# esp-12-f-breakout-ch340t.net
KiCad netlist of a schematic drawn in EAGLE
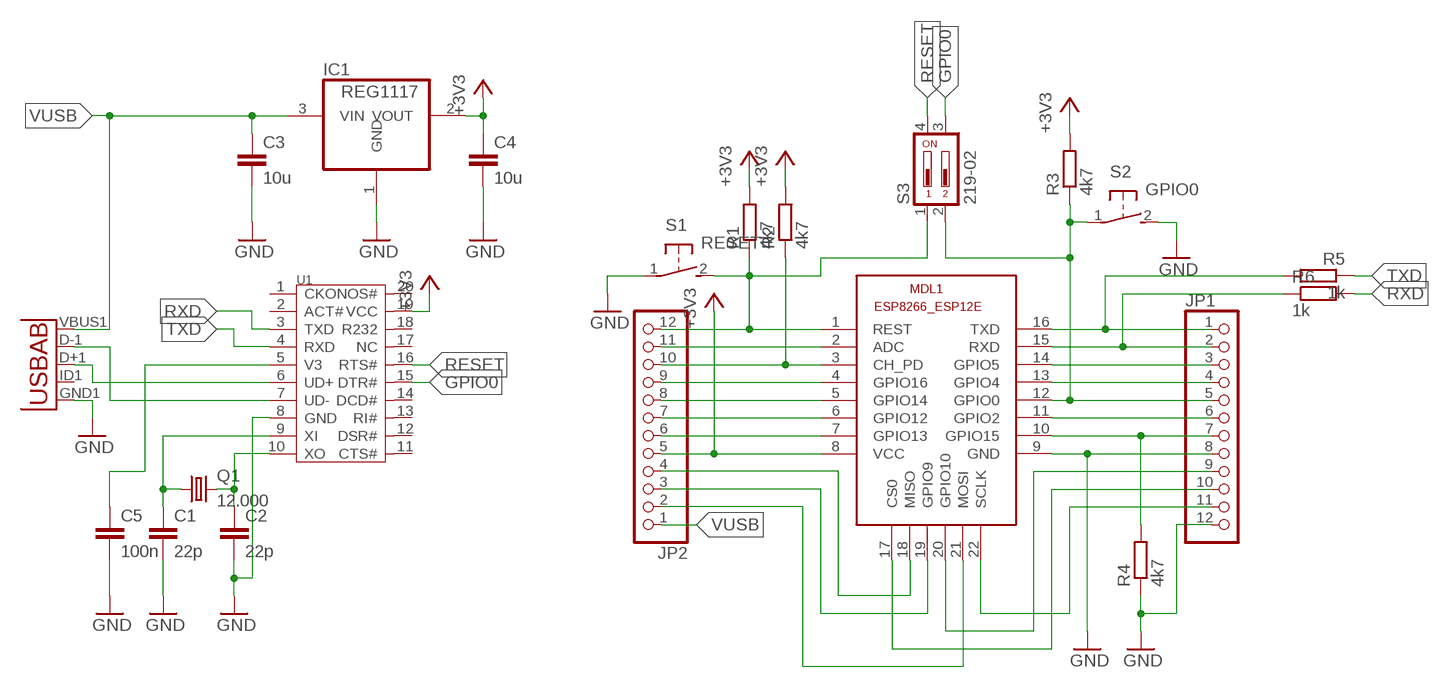
[diagram p0: schematic, sheet 1]

(export (version "E")
  (design (tool "Eeschema 10.0.6"))
  (components
    (comp (ref "C1")
      (value "22p")
      (footprint "eagle-import:C0805")
      (libsource (lib "eagle-import") (part "C-EUC0805"))
    )
    (comp (ref "C2")
      (value "22p")
      (footprint "eagle-import:C0805")
      (libsource (lib "eagle-import") (part "C-EUC0805"))
    )
    (comp (ref "C3")
      (value "10u")
      (footprint "eagle-import:C0805")
      (libsource (lib "eagle-import") (part "C-EUC0805"))
    )
    (comp (ref "C4")
      (value "10u")
      (footprint "eagle-import:C0805")
      (libsource (lib "eagle-import") (part "C-EUC0805"))
    )
    (comp (ref "C5")
      (value "100n")
      (footprint "eagle-import:C0805")
      (libsource (lib "eagle-import") (part "C-EUC0805"))
    )
    (comp (ref "IC1")
      (value "REG1117")
      (footprint "eagle-import:SOT223")
      (libsource (lib "eagle-import") (part "REG1117"))
    )
    (comp (ref "JP1")
      (value "PINHD-1X12")
      (footprint "eagle-import:1X12")
      (libsource (lib "eagle-import") (part "PINHD-1X12"))
    )
    (comp (ref "JP2")
      (value "PINHD-1X12")
      (footprint "eagle-import:1X12")
      (libsource (lib "eagle-import") (part "PINHD-1X12"))
    )
    (comp (ref "MDL1")
      (value "ESP8266-12EESP8266-ESP12E")
      (footprint "eagle-import:ESP8266-ESP12E")
      (libsource (lib "eagle-import") (part "ESP8266-12EESP8266-ESP12E"))
    )
    (comp (ref "Q1")
      (value "12.000")
      (footprint "eagle-import:HC49UP")
      (libsource (lib "eagle-import") (part "CRYSTALHC49UP"))
    )
    (comp (ref "R1")
      (value "4k7")
      (footprint "eagle-import:M0805")
      (libsource (lib "eagle-import") (part "R-EU_M0805"))
    )
    (comp (ref "R2")
      (value "4k7")
      (footprint "eagle-import:M0805")
      (libsource (lib "eagle-import") (part "R-EU_M0805"))
    )
    (comp (ref "R3")
      (value "4k7")
      (footprint "eagle-import:M0805")
      (libsource (lib "eagle-import") (part "R-EU_M0805"))
    )
    (comp (ref "R4")
      (value "4k7")
      (footprint "eagle-import:M0805")
      (libsource (lib "eagle-import") (part "R-EU_M0805"))
    )
    (comp (ref "R5")
      (value "1k")
      (footprint "eagle-import:M0805")
      (libsource (lib "eagle-import") (part "R-EU_M0805"))
    )
    (comp (ref "R6")
      (value "1k")
      (footprint "eagle-import:M0805")
      (libsource (lib "eagle-import") (part "R-EU_M0805"))
    )
    (comp (ref "S1")
      (value "RESET")
      (footprint "eagle-import:DTSM-3")
      (libsource (lib "eagle-import") (part "DTSM-3"))
    )
    (comp (ref "S2")
      (value "GPIO0")
      (footprint "eagle-import:DTSM-3")
      (libsource (lib "eagle-import") (part "DTSM-3"))
    )
    (comp (ref "S3")
      (value "219-02")
      (footprint "eagle-import:CTS-219-02")
      (libsource (lib "eagle-import") (part "219-02"))
    )
    (comp (ref "U1")
      (value "CH340T")
      (footprint "eagle-import:SSOP20")
      (libsource (lib "eagle-import") (part "CH340T"))
    )
    (comp (ref "U2")
      (value "USB\"\"")
      (footprint "eagle-import:USB-MICRO-SMD")
      (libsource (lib "eagle-import") (part "USB{dblquote}{dblquote}"))
    )
  )
  (nets
    (net (code "1") (name "+3V3") (class "Default")
      (node (ref "C4") (pin "1") (pinfunction "1_1") (pintype "passive"))
      (node (ref "IC1") (pin "2") (pinfunction "VOUT_2") (pintype "output"))
      (node (ref "JP2") (pin "5") (pinfunction "5_5") (pintype "passive"))
      (node (ref "MDL1") (pin "8") (pinfunction "VCC_8") (pintype "bidirectional"))
      (node (ref "R1") (pin "2") (pinfunction "2_2") (pintype "passive"))
      (node (ref "R2") (pin "2") (pinfunction "2_2") (pintype "passive"))
      (node (ref "R3") (pin "2") (pinfunction "2_2") (pintype "passive"))
      (node (ref "U1") (pin "19") (pinfunction "VCC_19") (pintype "power_in"))
    )
    (net (code "2") (name "/NOS#") (class "Default")
      (node (ref "U1") (pin "20") (pinfunction "NOS#_20") (pintype "power_in"))
    )
    (net (code "3") (name "GND") (class "Default")
      (node (ref "C1") (pin "2") (pinfunction "2_2") (pintype "passive"))
      (node (ref "C2") (pin "2") (pinfunction "2_2") (pintype "passive"))
      (node (ref "C3") (pin "2") (pinfunction "2_2") (pintype "passive"))
      (node (ref "C4") (pin "2") (pinfunction "2_2") (pintype "passive"))
      (node (ref "C5") (pin "2") (pinfunction "2_2") (pintype "passive"))
      (node (ref "IC1") (pin "1") (pinfunction "GND_1") (pintype "power_in"))
      (node (ref "JP1") (pin "12") (pinfunction "12_12") (pintype "passive"))
      (node (ref "JP1") (pin "8") (pinfunction "8_8") (pintype "passive"))
      (node (ref "MDL1") (pin "9") (pinfunction "GND_9") (pintype "bidirectional"))
      (node (ref "R4") (pin "1") (pinfunction "1_1") (pintype "passive"))
      (node (ref "S1") (pin "1") (pinfunction "1_1") (pintype "passive"))
      (node (ref "S2") (pin "2") (pinfunction "2_2") (pintype "passive"))
      (node (ref "U1") (pin "8") (pinfunction "GND_8") (pintype "power_in"))
      (node (ref "U2") (pin "GND1") (pinfunction "GND_GND1") (pintype "bidirectional"))
    )
    (net (code "4") (name "GPIO0") (class "Default")
      (node (ref "S3") (pin "3") (pinfunction "3_3") (pintype "passive"))
      (node (ref "U1") (pin "15") (pinfunction "DTR#_15") (pintype "output"))
    )
    (net (code "5") (name "Net-(MDL1-ADC)") (class "Default")
      (node (ref "JP2") (pin "11") (pinfunction "11_11") (pintype "passive"))
      (node (ref "MDL1") (pin "2") (pinfunction "ADC_2") (pintype "bidirectional"))
    )
    (net (code "6") (name "Net-(MDL1-CH_PD)") (class "Default")
      (node (ref "JP2") (pin "10") (pinfunction "10_10") (pintype "passive"))
      (node (ref "MDL1") (pin "3") (pinfunction "CH_PD_3") (pintype "bidirectional"))
      (node (ref "R2") (pin "1") (pinfunction "1_1") (pintype "passive"))
    )
    (net (code "7") (name "Net-(MDL1-CS0)") (class "Default")
      (node (ref "JP1") (pin "10") (pinfunction "10_10") (pintype "passive"))
      (node (ref "MDL1") (pin "17") (pinfunction "CS0_17") (pintype "bidirectional"))
    )
    (net (code "8") (name "Net-(MDL1-GPIO0)") (class "Default")
      (node (ref "JP1") (pin "5") (pinfunction "5_5") (pintype "passive"))
      (node (ref "MDL1") (pin "12") (pinfunction "GPIO0_12") (pintype "bidirectional"))
      (node (ref "R3") (pin "1") (pinfunction "1_1") (pintype "passive"))
      (node (ref "S2") (pin "1") (pinfunction "1_1") (pintype "passive"))
      (node (ref "S3") (pin "2") (pinfunction "2_2") (pintype "passive"))
    )
    (net (code "9") (name "Net-(MDL1-GPIO2)") (class "Default")
      (node (ref "JP1") (pin "6") (pinfunction "6_6") (pintype "passive"))
      (node (ref "MDL1") (pin "11") (pinfunction "GPIO2_11") (pintype "bidirectional"))
    )
    (net (code "10") (name "Net-(MDL1-GPIO4)") (class "Default")
      (node (ref "JP1") (pin "4") (pinfunction "4_4") (pintype "passive"))
      (node (ref "MDL1") (pin "13") (pinfunction "GPIO4_13") (pintype "bidirectional"))
    )
    (net (code "11") (name "Net-(MDL1-GPIO5)") (class "Default")
      (node (ref "JP1") (pin "3") (pinfunction "3_3") (pintype "passive"))
      (node (ref "MDL1") (pin "14") (pinfunction "GPIO5_14") (pintype "bidirectional"))
    )
    (net (code "12") (name "Net-(MDL1-GPIO9)") (class "Default")
      (node (ref "JP2") (pin "3") (pinfunction "3_3") (pintype "passive"))
      (node (ref "MDL1") (pin "19") (pinfunction "GPIO9_19") (pintype "bidirectional"))
    )
    (net (code "13") (name "Net-(MDL1-GPIO10)") (class "Default")
      (node (ref "JP1") (pin "9") (pinfunction "9_9") (pintype "passive"))
      (node (ref "MDL1") (pin "20") (pinfunction "GPIO10_20") (pintype "bidirectional"))
    )
    (net (code "14") (name "Net-(MDL1-GPIO12)") (class "Default")
      (node (ref "JP2") (pin "7") (pinfunction "7_7") (pintype "passive"))
      (node (ref "MDL1") (pin "6") (pinfunction "GPIO12_6") (pintype "bidirectional"))
    )
    (net (code "15") (name "Net-(MDL1-GPIO13)") (class "Default")
      (node (ref "JP2") (pin "6") (pinfunction "6_6") (pintype "passive"))
      (node (ref "MDL1") (pin "7") (pinfunction "GPIO13_7") (pintype "bidirectional"))
    )
    (net (code "16") (name "Net-(MDL1-GPIO14)") (class "Default")
      (node (ref "JP2") (pin "8") (pinfunction "8_8") (pintype "passive"))
      (node (ref "MDL1") (pin "5") (pinfunction "GPIO14_5") (pintype "bidirectional"))
    )
    (net (code "17") (name "Net-(MDL1-GPIO15)") (class "Default")
      (node (ref "JP1") (pin "7") (pinfunction "7_7") (pintype "passive"))
      (node (ref "MDL1") (pin "10") (pinfunction "GPIO15_10") (pintype "bidirectional"))
      (node (ref "R4") (pin "2") (pinfunction "2_2") (pintype "passive"))
    )
    (net (code "18") (name "Net-(MDL1-GPIO16)") (class "Default")
      (node (ref "JP2") (pin "9") (pinfunction "9_9") (pintype "passive"))
      (node (ref "MDL1") (pin "4") (pinfunction "GPIO16_4") (pintype "bidirectional"))
    )
    (net (code "19") (name "Net-(MDL1-MISO)") (class "Default")
      (node (ref "JP2") (pin "4") (pinfunction "4_4") (pintype "passive"))
      (node (ref "MDL1") (pin "18") (pinfunction "MISO_18") (pintype "bidirectional"))
    )
    (net (code "20") (name "Net-(MDL1-MOSI)") (class "Default")
      (node (ref "JP2") (pin "2") (pinfunction "2_2") (pintype "passive"))
      (node (ref "MDL1") (pin "21") (pinfunction "MOSI_21") (pintype "bidirectional"))
    )
    (net (code "21") (name "Net-(MDL1-REST)") (class "Default")
      (node (ref "JP2") (pin "12") (pinfunction "12_12") (pintype "passive"))
      (node (ref "MDL1") (pin "1") (pinfunction "REST_1") (pintype "bidirectional"))
      (node (ref "R1") (pin "1") (pinfunction "1_1") (pintype "passive"))
      (node (ref "S1") (pin "2") (pinfunction "2_2") (pintype "passive"))
      (node (ref "S3") (pin "1") (pinfunction "1_1") (pintype "passive"))
    )
    (net (code "22") (name "Net-(MDL1-RXD)") (class "Default")
      (node (ref "JP1") (pin "2") (pinfunction "2_2") (pintype "passive"))
      (node (ref "MDL1") (pin "15") (pinfunction "RXD_15") (pintype "bidirectional"))
      (node (ref "R6") (pin "1") (pinfunction "1_1") (pintype "passive"))
    )
    (net (code "23") (name "Net-(MDL1-SCLK)") (class "Default")
      (node (ref "JP1") (pin "11") (pinfunction "11_11") (pintype "passive"))
      (node (ref "MDL1") (pin "22") (pinfunction "SCLK_22") (pintype "bidirectional"))
    )
    (net (code "24") (name "Net-(MDL1-TXD)") (class "Default")
      (node (ref "JP1") (pin "1") (pinfunction "1_1") (pintype "passive"))
      (node (ref "MDL1") (pin "16") (pinfunction "TXD_16") (pintype "bidirectional"))
      (node (ref "R5") (pin "2") (pinfunction "2_2") (pintype "passive"))
    )
    (net (code "25") (name "Net-(U1-UD+)") (class "Default")
      (node (ref "U1") (pin "6") (pinfunction "UD+_6") (pintype "bidirectional"))
      (node (ref "U2") (pin "D+1") (pinfunction "D+_D+1") (pintype "bidirectional"))
    )
    (net (code "26") (name "Net-(U1-UD-)") (class "Default")
      (node (ref "U1") (pin "7") (pinfunction "UD-_7") (pintype "bidirectional"))
      (node (ref "U2") (pin "D-1") (pinfunction "D-_D-1") (pintype "bidirectional"))
    )
    (net (code "27") (name "Net-(U1-V3)") (class "Default")
      (node (ref "C5") (pin "1") (pinfunction "1_1") (pintype "passive"))
      (node (ref "U1") (pin "5") (pinfunction "V3_5") (pintype "power_in"))
    )
    (net (code "28") (name "Net-(U1-XI)") (class "Default")
      (node (ref "C1") (pin "1") (pinfunction "1_1") (pintype "passive"))
      (node (ref "Q1") (pin "1") (pinfunction "1_1") (pintype "passive"))
      (node (ref "U1") (pin "9") (pinfunction "XI_9") (pintype "input"))
    )
    (net (code "29") (name "Net-(U1-XO)") (class "Default")
      (node (ref "C2") (pin "1") (pinfunction "1_1") (pintype "passive"))
      (node (ref "Q1") (pin "2") (pinfunction "2_2") (pintype "passive"))
      (node (ref "U1") (pin "10") (pinfunction "XO_10") (pintype "output"))
    )
    (net (code "30") (name "RESET") (class "Default")
      (node (ref "S3") (pin "4") (pinfunction "4_4") (pintype "passive"))
      (node (ref "U1") (pin "16") (pinfunction "RTS#_16") (pintype "output"))
    )
    (net (code "31") (name "RXD") (class "Default")
      (node (ref "R6") (pin "2") (pinfunction "2_2") (pintype "passive"))
      (node (ref "U1") (pin "3") (pinfunction "TXD_3") (pintype "output"))
    )
    (net (code "32") (name "TXD") (class "Default")
      (node (ref "R5") (pin "1") (pinfunction "1_1") (pintype "passive"))
      (node (ref "U1") (pin "4") (pinfunction "RXD_4") (pintype "input"))
    )
    (net (code "33") (name "VUSB") (class "Default")
      (node (ref "C3") (pin "1") (pinfunction "1_1") (pintype "passive"))
      (node (ref "IC1") (pin "3") (pinfunction "VIN_3") (pintype "input"))
      (node (ref "JP2") (pin "1") (pinfunction "1_1") (pintype "passive"))
      (node (ref "U2") (pin "VBUS1") (pinfunction "VBUS_VBUS1") (pintype "bidirectional"))
    )
    (net (code "34") (name "unconnected-(U1-ACT#-Pad2)") (class "Default")
      (node (ref "U1") (pin "2") (pinfunction "ACT#_2") (pintype "output"))
    )
    (net (code "35") (name "unconnected-(U1-CKO-Pad1)") (class "Default")
      (node (ref "U1") (pin "1") (pinfunction "CKO_1") (pintype "output"))
    )
    (net (code "36") (name "unconnected-(U1-CTS#-Pad11)") (class "Default")
      (node (ref "U1") (pin "11") (pinfunction "CTS#_11") (pintype "input"))
    )
    (net (code "37") (name "unconnected-(U1-DCD#-Pad14)") (class "Default")
      (node (ref "U1") (pin "14") (pinfunction "DCD#_14") (pintype "input"))
    )
    (net (code "38") (name "unconnected-(U1-DSR#-Pad12)") (class "Default")
      (node (ref "U1") (pin "12") (pinfunction "DSR#_12") (pintype "input"))
    )
    (net (code "39") (name "unconnected-(U1-NC-Pad17)") (class "Default")
      (node (ref "U1") (pin "17") (pinfunction "NC_17") (pintype "no_connect"))
    )
    (net (code "40") (name "unconnected-(U1-R232-Pad18)") (class "Default")
      (node (ref "U1") (pin "18") (pinfunction "R232_18") (pintype "input"))
    )
    (net (code "41") (name "unconnected-(U1-RI#-Pad13)") (class "Default")
      (node (ref "U1") (pin "13") (pinfunction "RI#_13") (pintype "input"))
    )
    (net (code "42") (name "unconnected-(U2-USBID-PadID1)") (class "Default")
      (node (ref "U2") (pin "ID1") (pinfunction "USBID_ID1") (pintype "bidirectional"))
    )
  )
)
